# LTTO-medic-remote.net
KiCad netlist of a schematic drawn in EAGLE
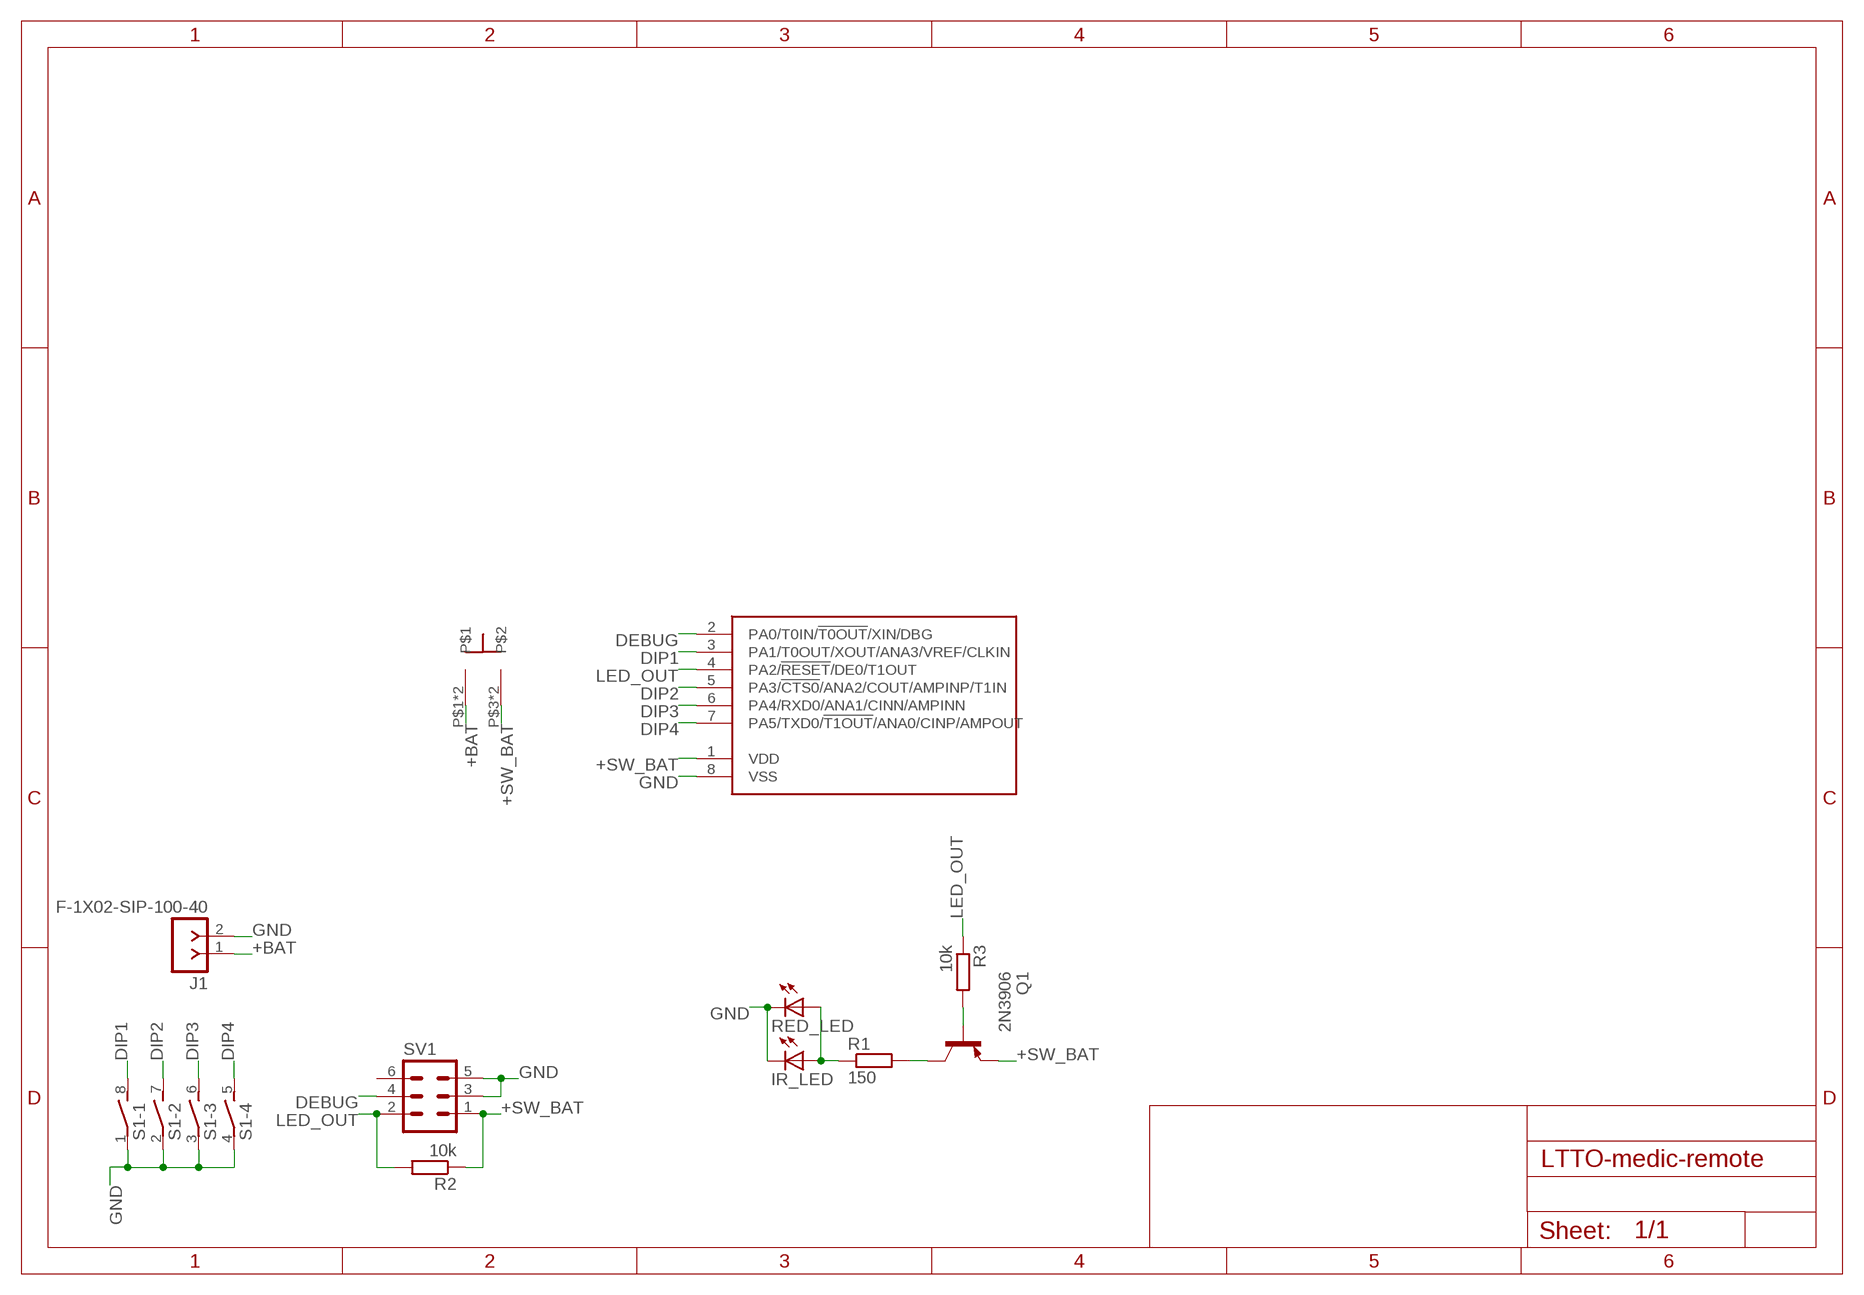
[diagram p0: schematic, sheet 1]

(export (version "E")
  (design (tool "Eeschema 10.0.6"))
  (components
    (comp (ref "IR_LED")
      (value "LED5MM")
      (footprint "eagle-import:LED5MM")
      (libsource (lib "eagle-import") (part "LED5MM"))
    )
    (comp (ref "J1")
      (value "F-1X02-SIP-100-40")
      (footprint "eagle-import:SIP-100-02-40")
      (libsource (lib "eagle-import") (part "F-1X02-SIP-100-40"))
    )
    (comp (ref "Q1")
      (value "2N3906")
      (footprint "eagle-import:TO92")
      (libsource (lib "eagle-import") (part "2N3906"))
    )
    (comp (ref "R1")
      (value "150")
      (footprint "eagle-import:0204_7")
      (libsource (lib "eagle-import") (part "R-EU_0204/7"))
    )
    (comp (ref "R2")
      (value "10k")
      (footprint "eagle-import:0204_7")
      (libsource (lib "eagle-import") (part "R-EU_0204/7"))
    )
    (comp (ref "R3")
      (value "10k")
      (footprint "eagle-import:0204_7")
      (libsource (lib "eagle-import") (part "R-EU_0204/7"))
    )
    (comp (ref "RED_LED")
      (value "LED5MM")
      (footprint "eagle-import:LED5MM")
      (libsource (lib "eagle-import") (part "LED5MM"))
    )
    (comp (ref "S1")
      (value "DIP04S")
      (footprint "eagle-import:DIP04S")
      (libsource (lib "eagle-import") (part "DIP04S"))
    )
    (comp (ref "SV1")
      (value "MA03-2")
      (footprint "eagle-import:MA03-2")
      (libsource (lib "eagle-import") (part "MA03-2"))
    )
    (comp (ref "U$1")
      (value "Z8F082ADIL-8")
      (footprint "eagle-import:DIL8")
      (libsource (lib "eagle-import") (part "Z8F082ADIL-8"))
    )
    (comp (ref "U$2")
      (value "PUSHBUTTON")
      (footprint "eagle-import:PUSHBUTTON")
      (libsource (lib "eagle-import") (part "PUSHBUTTON"))
    )
  )
  (nets
    (net (code "1") (name "/+BAT") (class "Default")
      (node (ref "J1") (pin "1") (pinfunction "1_1") (pintype "passive"))
      (node (ref "U$2") (pin "P$1") (pinfunction "P$1_P$1") (pintype "bidirectional"))
      (node (ref "U$2") (pin "P$2") (pinfunction "P$1_P$2") (pintype "bidirectional"))
    )
    (net (code "2") (name "/+SW_BAT") (class "Default")
      (node (ref "Q1") (pin "3") (pinfunction "E_3") (pintype "passive"))
      (node (ref "R2") (pin "1") (pinfunction "1_1") (pintype "passive"))
      (node (ref "SV1") (pin "1") (pinfunction "1_1") (pintype "passive"))
      (node (ref "U$1") (pin "1") (pinfunction "VDD_1") (pintype "bidirectional"))
      (node (ref "U$2") (pin "P$3") (pinfunction "P$2_P$3") (pintype "bidirectional"))
      (node (ref "U$2") (pin "P$4") (pinfunction "P$2_P$4") (pintype "bidirectional"))
    )
    (net (code "3") (name "/DEBUG") (class "Default")
      (node (ref "SV1") (pin "4") (pinfunction "4_4") (pintype "passive"))
      (node (ref "U$1") (pin "2") (pinfunction "PA0/T0IN/~{T0OUT}/XIN/DBG_2") (pintype "bidirectional"))
    )
    (net (code "4") (name "/DIP1") (class "Default")
      (node (ref "S1") (pin "8") (pinfunction "2_8") (pintype "passive"))
      (node (ref "U$1") (pin "3") (pinfunction "PA1/T0OUT/XOUT/ANA3/VREF/CLKIN_3") (pintype "bidirectional"))
    )
    (net (code "5") (name "/DIP2") (class "Default")
      (node (ref "S1") (pin "7") (pinfunction "2_7") (pintype "passive"))
      (node (ref "U$1") (pin "5") (pinfunction "PA3/~{CTS0}/ANA2/COUT/AMPINP/T1IN_5") (pintype "bidirectional"))
    )
    (net (code "6") (name "/DIP3") (class "Default")
      (node (ref "S1") (pin "6") (pinfunction "2_6") (pintype "passive"))
      (node (ref "U$1") (pin "6") (pinfunction "PA4/RXD0/ANA1/CINN/AMPINN_6") (pintype "bidirectional"))
    )
    (net (code "7") (name "/DIP4") (class "Default")
      (node (ref "S1") (pin "5") (pinfunction "2_5") (pintype "passive"))
      (node (ref "U$1") (pin "7") (pinfunction "PA5/TXD0/~{T1OUT}/ANA0/CINP/AMPOUT_7") (pintype "bidirectional"))
    )
    (net (code "8") (name "/GND") (class "Default")
      (node (ref "IR_LED") (pin "K") (pinfunction "C_K") (pintype "passive"))
      (node (ref "J1") (pin "2") (pinfunction "2_2") (pintype "passive"))
      (node (ref "RED_LED") (pin "K") (pinfunction "C_K") (pintype "passive"))
      (node (ref "S1") (pin "1") (pinfunction "1_1") (pintype "passive"))
      (node (ref "S1") (pin "2") (pinfunction "1_2") (pintype "passive"))
      (node (ref "S1") (pin "3") (pinfunction "1_3") (pintype "passive"))
      (node (ref "S1") (pin "4") (pinfunction "1_4") (pintype "passive"))
      (node (ref "SV1") (pin "3") (pinfunction "3_3") (pintype "passive"))
      (node (ref "SV1") (pin "5") (pinfunction "5_5") (pintype "passive"))
      (node (ref "U$1") (pin "8") (pinfunction "VSS_8") (pintype "bidirectional"))
    )
    (net (code "9") (name "/LED_OUT") (class "Default")
      (node (ref "R2") (pin "2") (pinfunction "2_2") (pintype "passive"))
      (node (ref "R3") (pin "1") (pinfunction "1_1") (pintype "passive"))
      (node (ref "SV1") (pin "2") (pinfunction "2_2") (pintype "passive"))
      (node (ref "U$1") (pin "4") (pinfunction "PA2/~{RESET}/DE0/T1OUT_4") (pintype "bidirectional"))
    )
    (net (code "10") (name "Net-(IR_LED-PadA)") (class "Default")
      (node (ref "IR_LED") (pin "A") (pinfunction "A_A") (pintype "passive"))
      (node (ref "R1") (pin "1") (pinfunction "1_1") (pintype "passive"))
      (node (ref "RED_LED") (pin "A") (pinfunction "A_A") (pintype "passive"))
    )
    (net (code "11") (name "Net-(Q1-B)") (class "Default")
      (node (ref "Q1") (pin "2") (pinfunction "B_2") (pintype "passive"))
      (node (ref "R3") (pin "2") (pinfunction "2_2") (pintype "passive"))
    )
    (net (code "12") (name "Net-(Q1-C)") (class "Default")
      (node (ref "Q1") (pin "1") (pinfunction "C_1") (pintype "passive"))
      (node (ref "R1") (pin "2") (pinfunction "2_2") (pintype "passive"))
    )
    (net (code "13") (name "unconnected-(SV1-Pad6)") (class "Default")
      (node (ref "SV1") (pin "6") (pinfunction "6_6") (pintype "passive"))
    )
  )
)
